# 1-Schematic_5C1555.net
KiCad netlist of a schematic drawn in EasyEDA
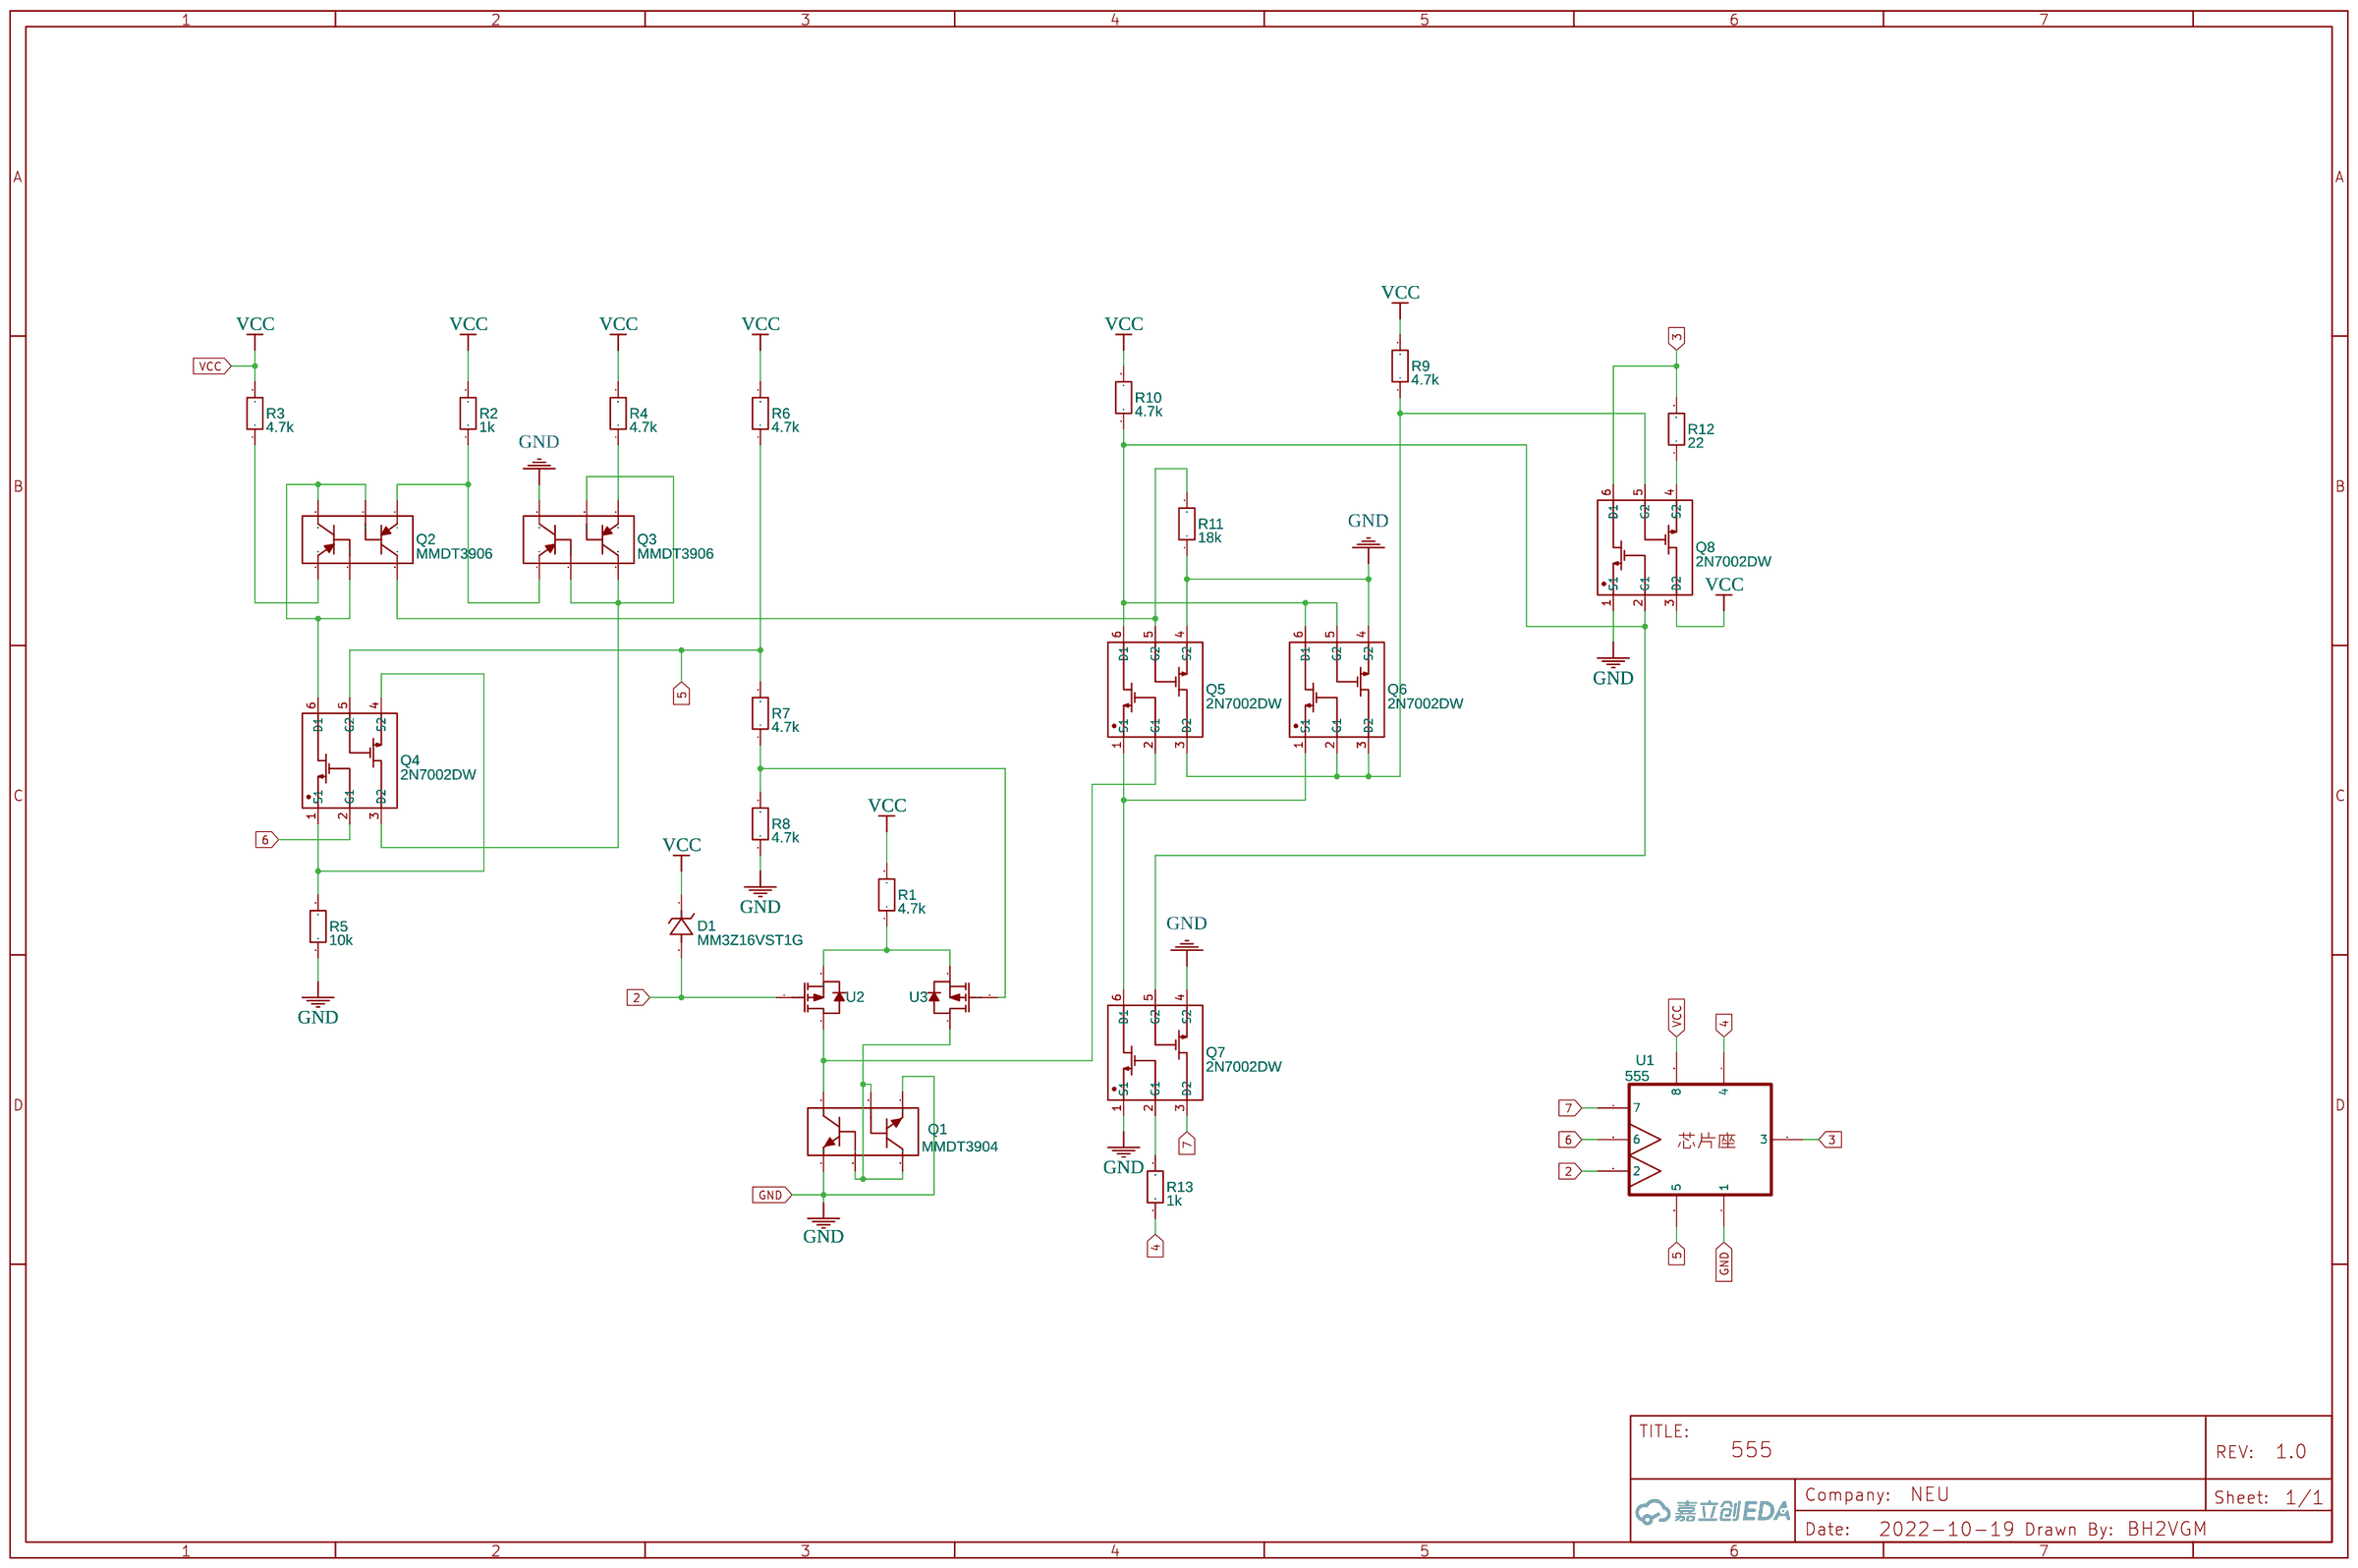
[diagram p0: schematic sheet]

(export (version "E")
  (design (tool "Eeschema 10.0.6"))
  (components
    (comp (ref "D1")
      (value "MM3Z16VST1G")
      (fields (field (name "BOM_Supplier Part") "C603317"))
      (libsource (lib "") (part "MM3Z16VST1G"))
    )
    (comp (ref "Q1")
      (value "MMDT3904")
      (fields
        (field (name "BOM_Manufacturer Part") "MMDT3904-7-F")
        (field (name "BOM_Supplier Part") "C83572")
      )
      (libsource (lib "") (part "MMDT3904"))
    )
    (comp (ref "Q2")
      (value "MMDT3906")
      (fields
        (field (name "BOM_Manufacturer Part") "MMDT3906-TP")
        (field (name "BOM_Supplier Part") "C779248")
      )
      (libsource (lib "") (part "MMDT3906"))
    )
    (comp (ref "Q3")
      (value "MMDT3906")
      (fields
        (field (name "BOM_Manufacturer Part") "MMDT3906-TP")
        (field (name "BOM_Supplier Part") "C779248")
      )
      (libsource (lib "") (part "MMDT3906"))
    )
    (comp (ref "Q4")
      (value "2N7002DW")
      (fields
        (field (name "BOM_Manufacturer Part") "2N7002DW-TP")
        (field (name "BOM_Supplier Part") "C194045")
      )
      (libsource (lib "") (part "2N7002DW"))
    )
    (comp (ref "Q5")
      (value "2N7002DW")
      (fields
        (field (name "BOM_Manufacturer Part") "2N7002DW-TP")
        (field (name "BOM_Supplier Part") "C194045")
      )
      (libsource (lib "") (part "2N7002DW"))
    )
    (comp (ref "Q6")
      (value "2N7002DW")
      (fields
        (field (name "BOM_Manufacturer Part") "2N7002DW-TP")
        (field (name "BOM_Supplier Part") "C194045")
      )
      (libsource (lib "") (part "2N7002DW"))
    )
    (comp (ref "Q7")
      (value "2N7002DW")
      (fields
        (field (name "BOM_Manufacturer Part") "2N7002DW-TP")
        (field (name "BOM_Supplier Part") "C194045")
      )
      (libsource (lib "") (part "2N7002DW"))
    )
    (comp (ref "Q8")
      (value "2N7002DW")
      (fields
        (field (name "BOM_Manufacturer Part") "2N7002DW-TP")
        (field (name "BOM_Supplier Part") "C194045")
      )
      (libsource (lib "") (part "2N7002DW"))
    )
    (comp (ref "R1")
      (value "4.7k")
      (fields
        (field (name "BOM_Manufacturer Part") "HoLR0805-1/2W-10mR-1%")
        (field (name "BOM_Supplier Part") "C2912660")
      )
      (libsource (lib "") (part "HOLR0805-1/2W-10MR-1%"))
    )
    (comp (ref "R2")
      (value "1k")
      (fields
        (field (name "BOM_Manufacturer Part") "HoLR0805-1/2W-10mR-1%")
        (field (name "BOM_Supplier Part") "C2912660")
      )
      (libsource (lib "") (part "HOLR0805-1/2W-10MR-1%"))
    )
    (comp (ref "R3")
      (value "4.7k")
      (fields
        (field (name "BOM_Manufacturer Part") "HoLR0805-1/2W-10mR-1%")
        (field (name "BOM_Supplier Part") "C2912660")
      )
      (libsource (lib "") (part "HOLR0805-1/2W-10MR-1%"))
    )
    (comp (ref "R4")
      (value "4.7k")
      (fields
        (field (name "BOM_Manufacturer Part") "HoLR0805-1/2W-10mR-1%")
        (field (name "BOM_Supplier Part") "C2912660")
      )
      (libsource (lib "") (part "HOLR0805-1/2W-10MR-1%"))
    )
    (comp (ref "R5")
      (value "10k")
      (fields
        (field (name "BOM_Manufacturer Part") "HoLR0805-1/2W-10mR-1%")
        (field (name "BOM_Supplier Part") "C2912660")
      )
      (libsource (lib "") (part "HOLR0805-1/2W-10MR-1%"))
    )
    (comp (ref "R6")
      (value "4.7k")
      (fields
        (field (name "BOM_Manufacturer Part") "HoLR0805-1/2W-10mR-1%")
        (field (name "BOM_Supplier Part") "C2912660")
      )
      (libsource (lib "") (part "HOLR0805-1/2W-10MR-1%"))
    )
    (comp (ref "R7")
      (value "4.7k")
      (fields
        (field (name "BOM_Manufacturer Part") "HoLR0805-1/2W-10mR-1%")
        (field (name "BOM_Supplier Part") "C2912660")
      )
      (libsource (lib "") (part "HOLR0805-1/2W-10MR-1%"))
    )
    (comp (ref "R8")
      (value "4.7k")
      (fields
        (field (name "BOM_Manufacturer Part") "HoLR0805-1/2W-10mR-1%")
        (field (name "BOM_Supplier Part") "C2912660")
      )
      (libsource (lib "") (part "HOLR0805-1/2W-10MR-1%"))
    )
    (comp (ref "R9")
      (value "4.7k")
      (fields
        (field (name "BOM_Manufacturer Part") "HoLR0805-1/2W-10mR-1%")
        (field (name "BOM_Supplier Part") "C2912660")
      )
      (libsource (lib "") (part "HOLR0805-1/2W-10MR-1%"))
    )
    (comp (ref "R10")
      (value "4.7k")
      (fields
        (field (name "BOM_Manufacturer Part") "HoLR0805-1/2W-10mR-1%")
        (field (name "BOM_Supplier Part") "C2912660")
      )
      (libsource (lib "") (part "HOLR0805-1/2W-10MR-1%"))
    )
    (comp (ref "R11")
      (value "18k")
      (fields
        (field (name "BOM_Manufacturer Part") "HoLR0805-1/2W-10mR-1%")
        (field (name "BOM_Supplier Part") "C2912660")
      )
      (libsource (lib "") (part "HOLR0805-1/2W-10MR-1%"))
    )
    (comp (ref "R12")
      (value "22")
      (fields
        (field (name "BOM_Manufacturer Part") "HoLR0805-1/2W-10mR-1%")
        (field (name "BOM_Supplier Part") "C2912660")
      )
      (libsource (lib "") (part "HOLR0805-1/2W-10MR-1%"))
    )
    (comp (ref "R13")
      (value "1k")
      (fields
        (field (name "BOM_Manufacturer Part") "HoLR0805-1/2W-10mR-1%")
        (field (name "BOM_Supplier Part") "C2912660")
      )
      (libsource (lib "") (part "HOLR0805-1/2W-10MR-1%"))
    )
    (comp (ref "U1") (value "555") (libsource (lib "") (part "555")))
    (comp (ref "U2")
      (value "BSS84-H")
      (fields (field (name "BOM_Supplier Part") "C890268"))
      (libsource (lib "") (part "BSS84-H"))
    )
    (comp (ref "U3")
      (value "BSS84-H")
      (fields (field (name "BOM_Supplier Part") "C890268"))
      (libsource (lib "") (part "BSS84-H_1"))
    )
  )
  (nets
    (net (code "1") (name "2") (class "Default")
      (node (ref "D1") (pin "2") (pinfunction "A_2") (pintype "unspecified"))
      (node (ref "U1") (pin "2") (pinfunction "2_2") (pintype "unspecified"))
      (node (ref "U2") (pin "1") (pinfunction "G_1") (pintype "unspecified"))
    )
    (net (code "2") (name "3") (class "Default")
      (node (ref "Q8") (pin "6") (pinfunction "D1_6") (pintype "unspecified"))
      (node (ref "R12") (pin "2") (pinfunction "2_2") (pintype "unspecified"))
      (node (ref "U1") (pin "3") (pinfunction "3_3") (pintype "unspecified"))
    )
    (net (code "3") (name "4") (class "Default")
      (node (ref "R13") (pin "1") (pinfunction "1_1") (pintype "unspecified"))
      (node (ref "U1") (pin "4") (pinfunction "4_4") (pintype "unspecified"))
    )
    (net (code "4") (name "5") (class "Default")
      (node (ref "Q4") (pin "5") (pinfunction "G2_5") (pintype "unspecified"))
      (node (ref "R6") (pin "1") (pinfunction "1_1") (pintype "unspecified"))
      (node (ref "R7") (pin "2") (pinfunction "2_2") (pintype "unspecified"))
      (node (ref "U1") (pin "5") (pinfunction "5_5") (pintype "unspecified"))
    )
    (net (code "5") (name "6") (class "Default")
      (node (ref "Q4") (pin "2") (pinfunction "G1_2") (pintype "unspecified"))
      (node (ref "U1") (pin "6") (pinfunction "6_6") (pintype "unspecified"))
    )
    (net (code "6") (name "7") (class "Default")
      (node (ref "Q7") (pin "3") (pinfunction "D2_3") (pintype "unspecified"))
      (node (ref "U1") (pin "7") (pinfunction "7_7") (pintype "unspecified"))
    )
    (net (code "7") (name "GND") (class "Default")
      (node (ref "Q1") (pin "1") (pinfunction "E_1") (pintype "unspecified"))
      (node (ref "Q1") (pin "4") (pinfunction "E_4") (pintype "unspecified"))
      (node (ref "Q3") (pin "6") (pinfunction "C_6") (pintype "unspecified"))
      (node (ref "Q5") (pin "4") (pinfunction "S2_4") (pintype "unspecified"))
      (node (ref "Q6") (pin "4") (pinfunction "S2_4") (pintype "unspecified"))
      (node (ref "Q7") (pin "1") (pinfunction "S1_1") (pintype "unspecified"))
      (node (ref "Q7") (pin "4") (pinfunction "S2_4") (pintype "unspecified"))
      (node (ref "Q8") (pin "1") (pinfunction "S1_1") (pintype "unspecified"))
      (node (ref "R11") (pin "1") (pinfunction "1_1") (pintype "unspecified"))
      (node (ref "R5") (pin "1") (pinfunction "1_1") (pintype "unspecified"))
      (node (ref "R8") (pin "1") (pinfunction "1_1") (pintype "unspecified"))
      (node (ref "U1") (pin "1") (pinfunction "1_1") (pintype "unspecified"))
    )
    (net (code "8") (name "Net-(Q2-E-Pad1)") (class "Default")
      (node (ref "Q2") (pin "1") (pinfunction "E_1") (pintype "unspecified"))
      (node (ref "R3") (pin "1") (pinfunction "1_1") (pintype "unspecified"))
    )
    (net (code "9") (name "Net-(Q2-E-Pad4)") (class "Default")
      (node (ref "Q2") (pin "4") (pinfunction "E_4") (pintype "unspecified"))
      (node (ref "Q3") (pin "1") (pinfunction "E_1") (pintype "unspecified"))
      (node (ref "R2") (pin "1") (pinfunction "1_1") (pintype "unspecified"))
    )
    (net (code "10") (name "Net-(Q3-E-Pad4)") (class "Default")
      (node (ref "Q3") (pin "4") (pinfunction "E_4") (pintype "unspecified"))
      (node (ref "R4") (pin "1") (pinfunction "1_1") (pintype "unspecified"))
    )
    (net (code "11") (name "Net-(Q4-D1)") (class "Default")
      (node (ref "Q2") (pin "2") (pinfunction "B_2") (pintype "unspecified"))
      (node (ref "Q2") (pin "5") (pinfunction "B_5") (pintype "unspecified"))
      (node (ref "Q2") (pin "6") (pinfunction "C_6") (pintype "unspecified"))
      (node (ref "Q4") (pin "6") (pinfunction "D1_6") (pintype "unspecified"))
    )
    (net (code "12") (name "Net-(Q4-D2)") (class "Default")
      (node (ref "Q3") (pin "2") (pinfunction "B_2") (pintype "unspecified"))
      (node (ref "Q3") (pin "3") (pinfunction "C_3") (pintype "unspecified"))
      (node (ref "Q3") (pin "5") (pinfunction "B_5") (pintype "unspecified"))
      (node (ref "Q4") (pin "3") (pinfunction "D2_3") (pintype "unspecified"))
    )
    (net (code "13") (name "Net-(Q4-S1)") (class "Default")
      (node (ref "Q4") (pin "1") (pinfunction "S1_1") (pintype "unspecified"))
      (node (ref "Q4") (pin "4") (pinfunction "S2_4") (pintype "unspecified"))
      (node (ref "R5") (pin "2") (pinfunction "2_2") (pintype "unspecified"))
    )
    (net (code "14") (name "Net-(Q5-D1)") (class "Default")
      (node (ref "Q5") (pin "6") (pinfunction "D1_6") (pintype "unspecified"))
      (node (ref "Q6") (pin "5") (pinfunction "G2_5") (pintype "unspecified"))
      (node (ref "Q6") (pin "6") (pinfunction "D1_6") (pintype "unspecified"))
      (node (ref "Q7") (pin "5") (pinfunction "G2_5") (pintype "unspecified"))
      (node (ref "Q8") (pin "2") (pinfunction "G1_2") (pintype "unspecified"))
      (node (ref "R10") (pin "1") (pinfunction "1_1") (pintype "unspecified"))
    )
    (net (code "15") (name "Net-(Q5-D2)") (class "Default")
      (node (ref "Q5") (pin "3") (pinfunction "D2_3") (pintype "unspecified"))
      (node (ref "Q6") (pin "2") (pinfunction "G1_2") (pintype "unspecified"))
      (node (ref "Q6") (pin "3") (pinfunction "D2_3") (pintype "unspecified"))
      (node (ref "Q8") (pin "5") (pinfunction "G2_5") (pintype "unspecified"))
      (node (ref "R9") (pin "1") (pinfunction "1_1") (pintype "unspecified"))
    )
    (net (code "16") (name "Net-(Q5-G1)") (class "Default")
      (node (ref "Q1") (pin "6") (pinfunction "C_6") (pintype "unspecified"))
      (node (ref "Q5") (pin "2") (pinfunction "G1_2") (pintype "unspecified"))
      (node (ref "U2") (pin "3") (pinfunction "D_3") (pintype "unspecified"))
    )
    (net (code "17") (name "Net-(Q5-G2)") (class "Default")
      (node (ref "Q2") (pin "3") (pinfunction "C_3") (pintype "unspecified"))
      (node (ref "Q5") (pin "5") (pinfunction "G2_5") (pintype "unspecified"))
      (node (ref "R11") (pin "2") (pinfunction "2_2") (pintype "unspecified"))
    )
    (net (code "18") (name "Net-(Q5-S1)") (class "Default")
      (node (ref "Q5") (pin "1") (pinfunction "S1_1") (pintype "unspecified"))
      (node (ref "Q6") (pin "1") (pinfunction "S1_1") (pintype "unspecified"))
      (node (ref "Q7") (pin "6") (pinfunction "D1_6") (pintype "unspecified"))
    )
    (net (code "19") (name "Net-(Q7-G1)") (class "Default")
      (node (ref "Q7") (pin "2") (pinfunction "G1_2") (pintype "unspecified"))
      (node (ref "R13") (pin "2") (pinfunction "2_2") (pintype "unspecified"))
    )
    (net (code "20") (name "Net-(Q8-S2)") (class "Default")
      (node (ref "Q8") (pin "4") (pinfunction "S2_4") (pintype "unspecified"))
      (node (ref "R12") (pin "1") (pinfunction "1_1") (pintype "unspecified"))
    )
    (net (code "21") (name "Net-(U2-S)") (class "Default")
      (node (ref "R1") (pin "1") (pinfunction "1_1") (pintype "unspecified"))
      (node (ref "U2") (pin "2") (pinfunction "S_2") (pintype "unspecified"))
      (node (ref "U3") (pin "2") (pinfunction "S_2") (pintype "unspecified"))
    )
    (net (code "22") (name "Net-(U3-D)") (class "Default")
      (node (ref "Q1") (pin "2") (pinfunction "B_2") (pintype "unspecified"))
      (node (ref "Q1") (pin "3") (pinfunction "C_3") (pintype "unspecified"))
      (node (ref "Q1") (pin "5") (pinfunction "B_5") (pintype "unspecified"))
      (node (ref "U3") (pin "3") (pinfunction "D_3") (pintype "unspecified"))
    )
    (net (code "23") (name "Net-(U3-G)") (class "Default")
      (node (ref "R7") (pin "1") (pinfunction "1_1") (pintype "unspecified"))
      (node (ref "R8") (pin "2") (pinfunction "2_2") (pintype "unspecified"))
      (node (ref "U3") (pin "1") (pinfunction "G_1") (pintype "unspecified"))
    )
    (net (code "24") (name "VCC") (class "Default")
      (node (ref "D1") (pin "1") (pinfunction "K_1") (pintype "unspecified"))
      (node (ref "Q8") (pin "3") (pinfunction "D2_3") (pintype "unspecified"))
      (node (ref "R1") (pin "2") (pinfunction "2_2") (pintype "unspecified"))
      (node (ref "R10") (pin "2") (pinfunction "2_2") (pintype "unspecified"))
      (node (ref "R2") (pin "2") (pinfunction "2_2") (pintype "unspecified"))
      (node (ref "R3") (pin "2") (pinfunction "2_2") (pintype "unspecified"))
      (node (ref "R4") (pin "2") (pinfunction "2_2") (pintype "unspecified"))
      (node (ref "R6") (pin "2") (pinfunction "2_2") (pintype "unspecified"))
      (node (ref "R9") (pin "2") (pinfunction "2_2") (pintype "unspecified"))
      (node (ref "U1") (pin "8") (pinfunction "8_8") (pintype "unspecified"))
    )
  )
)
